# untitled.net
KiCad netlist of a schematic drawn in EAGLE
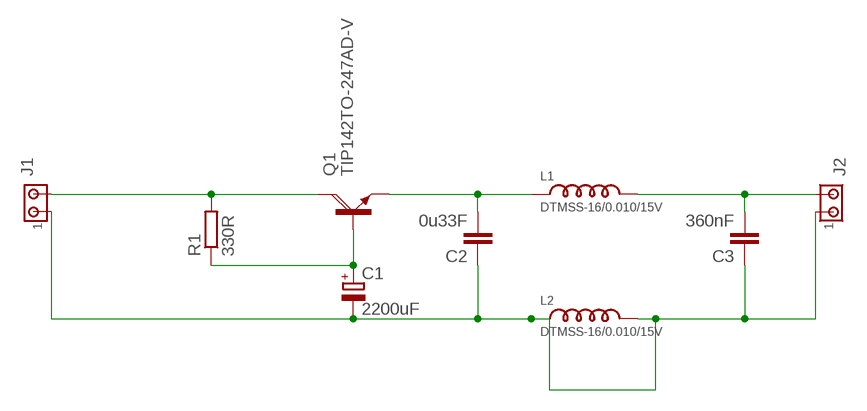
[diagram p0: schematic, sheet 1]

(export (version "E")
  (design (tool "Eeschema 10.0.6"))
  (components
    (comp (ref "C1")
      (value "2200uF")
      (footprint "eagle-import:E5-13")
      (libsource (lib "eagle-import") (part "CPOL-EUE5-13"))
    )
    (comp (ref "C2")
      (value "0u33F")
      (footprint "eagle-import:C102-054X133")
      (libsource (lib "eagle-import") (part "C-EU102-054X133"))
    )
    (comp (ref "C3")
      (value "360nF")
      (footprint "eagle-import:C102-054X133")
      (libsource (lib "eagle-import") (part "C-EU102-054X133"))
    )
    (comp (ref "J1")
      (value "MTA02-100")
      (footprint "eagle-import:10X02MTA")
      (libsource (lib "eagle-import") (part "MTA02-100"))
    )
    (comp (ref "J2")
      (value "MTA02-100")
      (footprint "eagle-import:10X02MTA")
      (libsource (lib "eagle-import") (part "MTA02-100"))
    )
    (comp (ref "L1")
      (value "DTMSS-16/0.010/15V")
      (footprint "eagle-import:DTMSS-16_0.010_15-V")
      (libsource (lib "eagle-import") (part "DTMSS-16/0.010/15V"))
    )
    (comp (ref "L2")
      (value "DTMSS-16/0.010/15V")
      (footprint "eagle-import:DTMSS-16_0.010_15-V")
      (libsource (lib "eagle-import") (part "DTMSS-16/0.010/15V"))
    )
    (comp (ref "Q1")
      (value "TIP142TO-247AD-V")
      (footprint "eagle-import:TO-247AD-V")
      (libsource (lib "eagle-import") (part "TIP142TO-247AD-V"))
    )
    (comp (ref "R1")
      (value "330R")
      (footprint "eagle-import:VTA52")
      (libsource (lib "eagle-import") (part "R-EU_VTA52"))
    )
  )
  (nets
    (net (code "1") (name "Net-(C1-Pad-)") (class "Default")
      (node (ref "C1") (pin "-") (pinfunction "-_-") (pintype "passive"))
      (node (ref "C2") (pin "1") (pinfunction "1_1") (pintype "passive"))
      (node (ref "C3") (pin "1") (pinfunction "1_1") (pintype "passive"))
      (node (ref "J1") (pin "1") (pinfunction "1_1") (pintype "passive"))
      (node (ref "J2") (pin "1") (pinfunction "1_1") (pintype "passive"))
      (node (ref "L2") (pin "P$1") (pinfunction "P$1_P$1") (pintype "bidirectional"))
      (node (ref "L2") (pin "P$2") (pinfunction "P$2_P$2") (pintype "bidirectional"))
    )
    (net (code "2") (name "Net-(C3-Pad2)") (class "Default")
      (node (ref "C3") (pin "2") (pinfunction "2_2") (pintype "passive"))
      (node (ref "J2") (pin "2") (pinfunction "2_2") (pintype "passive"))
      (node (ref "L1") (pin "P$2") (pinfunction "P$2_P$2") (pintype "bidirectional"))
    )
    (net (code "3") (name "Net-(Q1-B)") (class "Default")
      (node (ref "C1") (pin "+") (pinfunction "+_+") (pintype "passive"))
      (node (ref "Q1") (pin "G") (pinfunction "B_G") (pintype "passive"))
      (node (ref "R1") (pin "1") (pinfunction "1_1") (pintype "passive"))
    )
    (net (code "4") (name "Net-(Q1-C)") (class "Default")
      (node (ref "J1") (pin "2") (pinfunction "2_2") (pintype "passive"))
      (node (ref "Q1") (pin "D") (pinfunction "C_D") (pintype "passive"))
      (node (ref "R1") (pin "2") (pinfunction "2_2") (pintype "passive"))
    )
    (net (code "5") (name "Net-(Q1-E)") (class "Default")
      (node (ref "C2") (pin "2") (pinfunction "2_2") (pintype "passive"))
      (node (ref "L1") (pin "P$1") (pinfunction "P$1_P$1") (pintype "bidirectional"))
      (node (ref "Q1") (pin "S") (pinfunction "E_S") (pintype "passive"))
    )
  )
)
